# SchematicFinal.net
KiCad netlist of a schematic drawn in EAGLE
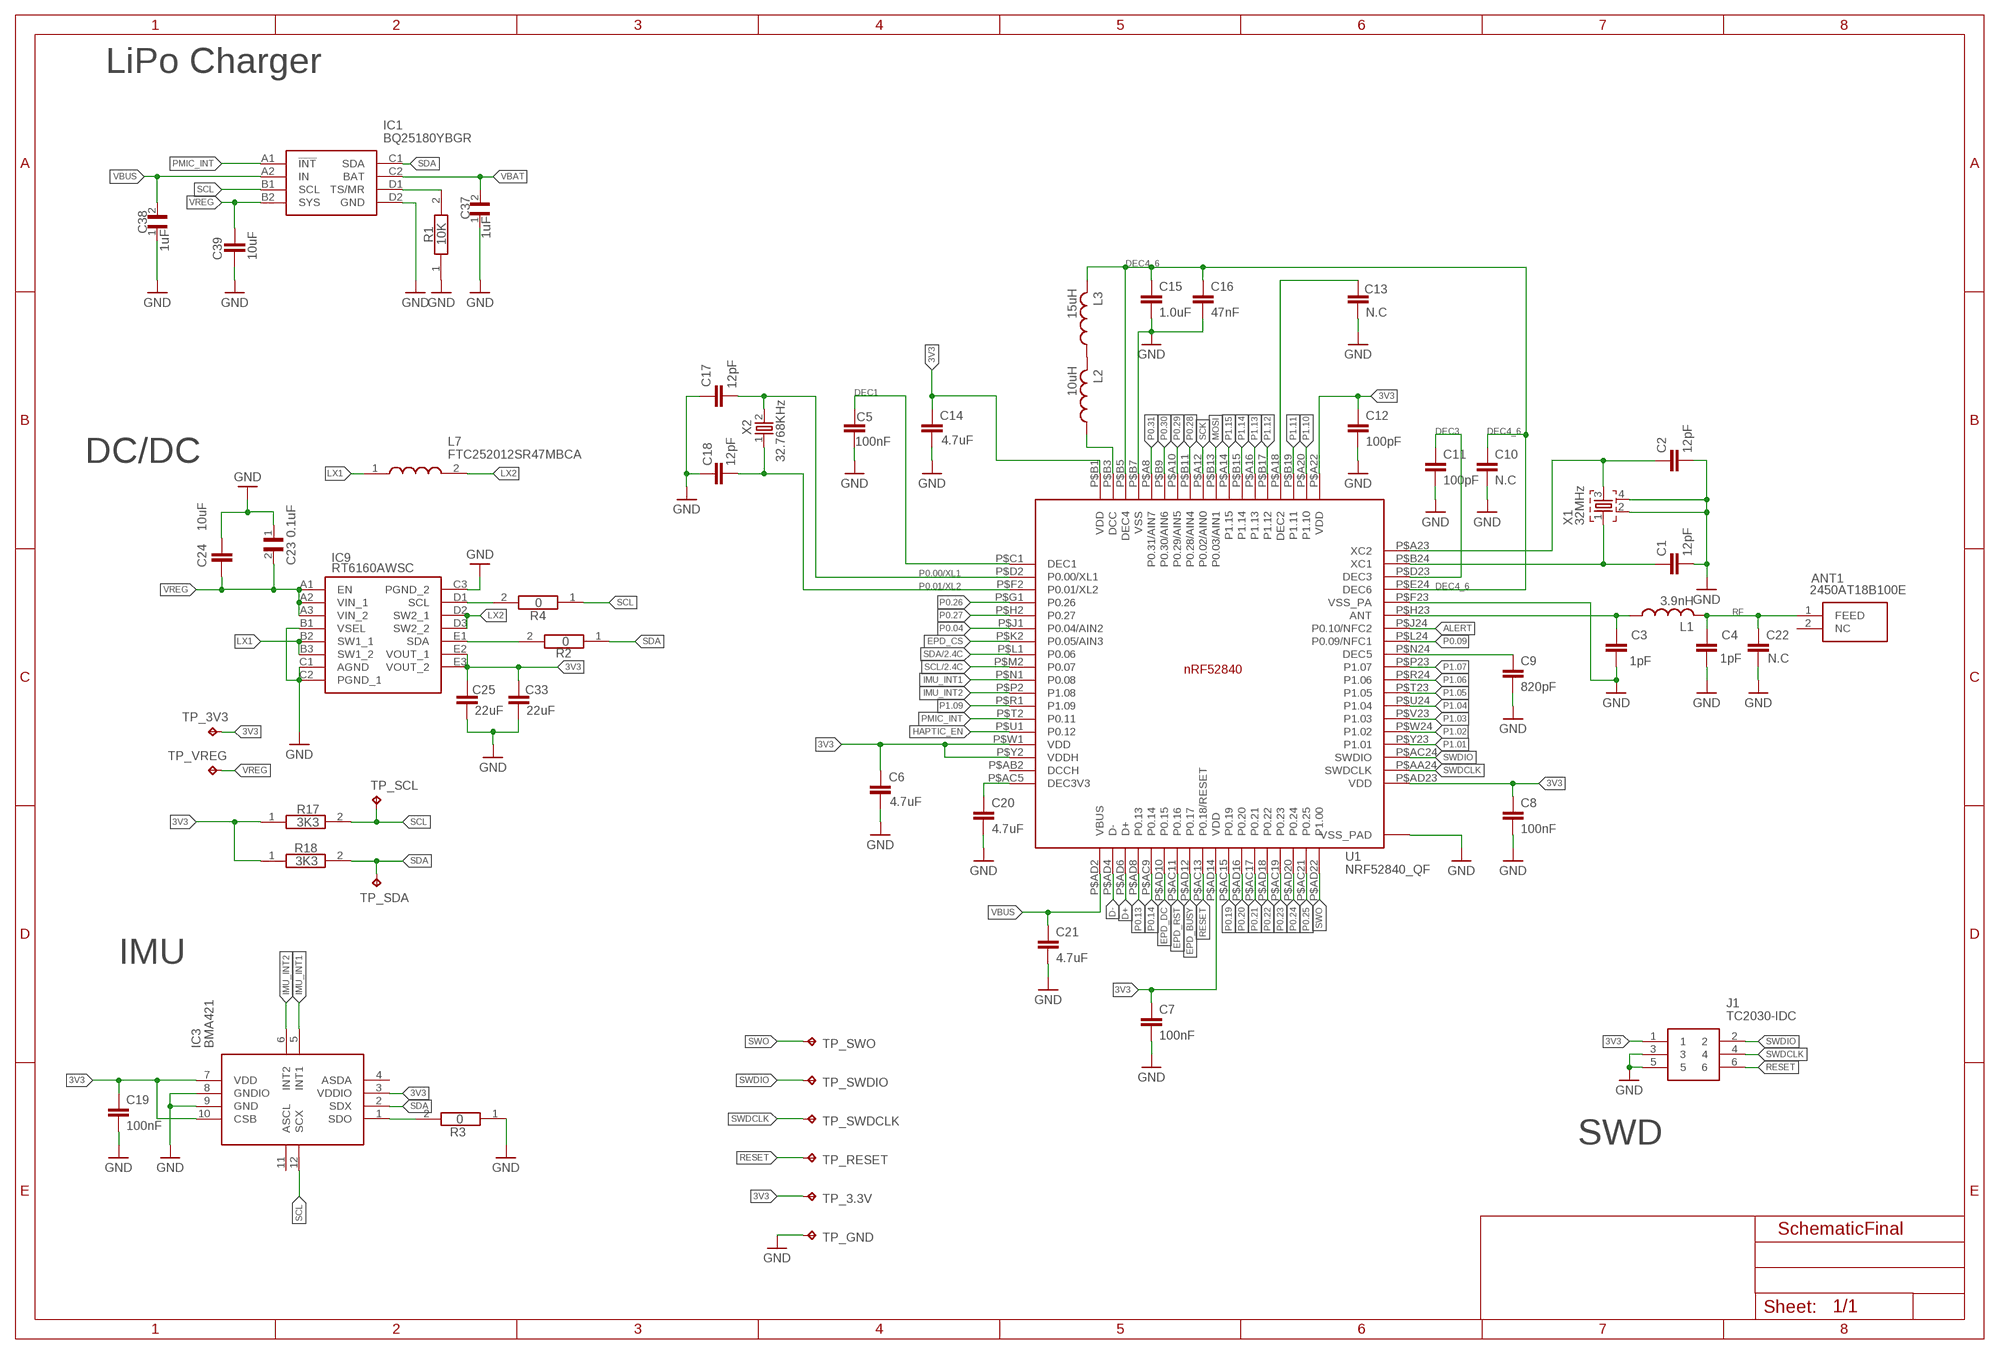
[diagram p0: schematic, sheet 1]

(export (version "E")
  (design (tool "Eeschema 10.0.6"))
  (components
    (comp (ref "ANT1")
      (value "2450AT18B100E")
      (footprint "eagle-import:2450AT18B100E_ANTC3216X140N")
      (fields (field (name "MOUSER_PART_NUMBER") "609-2450AT18B100E"))
      (libsource (lib "eagle-import") (part "2450AT18B100E_2450AT18B100E"))
    )
    (comp (ref "C1")
      (value "12pF")
      (footprint "eagle-import:NORDIC_NRF_3_RESC0402_M")
      (libsource (lib "eagle-import") (part "NORDIC_NRF_3_CAPACITOR_0402_M"))
    )
    (comp (ref "C2")
      (value "12pF")
      (footprint "eagle-import:NORDIC_NRF_3_RESC0402_M")
      (libsource (lib "eagle-import") (part "NORDIC_NRF_3_CAPACITOR_0402_M"))
    )
    (comp (ref "C3")
      (value "1pF")
      (footprint "eagle-import:NORDIC_NRF_3_RESC0402_M")
      (libsource (lib "eagle-import") (part "NORDIC_NRF_3_CAPACITOR_0402_M"))
    )
    (comp (ref "C4")
      (value "1pF")
      (footprint "eagle-import:NORDIC_NRF_3_RESC0402_M")
      (libsource (lib "eagle-import") (part "NORDIC_NRF_3_CAPACITOR_0402_M"))
    )
    (comp (ref "C5")
      (value "100nF")
      (footprint "eagle-import:NORDIC_NRF_3_RESC0402_M")
      (libsource (lib "eagle-import") (part "NORDIC_NRF_3_CAPACITOR_0402_M"))
    )
    (comp (ref "C6")
      (value "4.7uF")
      (footprint "eagle-import:NORDIC_NRF_3_RESC0402_M")
      (libsource (lib "eagle-import") (part "NORDIC_NRF_3_CAPACITOR_0402_M"))
    )
    (comp (ref "C7")
      (value "100nF")
      (footprint "eagle-import:NORDIC_NRF_3_RESC0402_M")
      (libsource (lib "eagle-import") (part "NORDIC_NRF_3_CAPACITOR_0402_M"))
    )
    (comp (ref "C8")
      (value "100nF")
      (footprint "eagle-import:NORDIC_NRF_3_RESC0402_M")
      (libsource (lib "eagle-import") (part "NORDIC_NRF_3_CAPACITOR_0402_M"))
    )
    (comp (ref "C9")
      (value "820pF")
      (footprint "eagle-import:NORDIC_NRF_3_RESC0402_M")
      (libsource (lib "eagle-import") (part "NORDIC_NRF_3_CAPACITOR_0402_M"))
    )
    (comp (ref "C10")
      (value "N.C")
      (footprint "eagle-import:NORDIC_NRF_3_RESC0402_M")
      (libsource (lib "eagle-import") (part "NORDIC_NRF_3_CAPACITOR_0402_M"))
    )
    (comp (ref "C11")
      (value "100pF")
      (footprint "eagle-import:NORDIC_NRF_3_RESC0402_M")
      (libsource (lib "eagle-import") (part "NORDIC_NRF_3_CAPACITOR_0402_M"))
    )
    (comp (ref "C12")
      (value "100pF")
      (footprint "eagle-import:NORDIC_NRF_3_RESC0402_M")
      (libsource (lib "eagle-import") (part "NORDIC_NRF_3_CAPACITOR_0402_M"))
    )
    (comp (ref "C13")
      (value "N.C")
      (footprint "eagle-import:NORDIC_NRF_3_RESC0402_M")
      (libsource (lib "eagle-import") (part "NORDIC_NRF_3_CAPACITOR_0402_M"))
    )
    (comp (ref "C14")
      (value "4.7uF")
      (footprint "eagle-import:NORDIC_NRF_3_RESC0402_M")
      (libsource (lib "eagle-import") (part "NORDIC_NRF_3_CAPACITOR_0402_M"))
    )
    (comp (ref "C15")
      (value "1.0uF")
      (footprint "eagle-import:NORDIC_NRF_3_RESC0402_M")
      (libsource (lib "eagle-import") (part "NORDIC_NRF_3_CAPACITOR_0402_M"))
    )
    (comp (ref "C16")
      (value "47nF")
      (footprint "eagle-import:NORDIC_NRF_3_RESC0402_M")
      (libsource (lib "eagle-import") (part "NORDIC_NRF_3_CAPACITOR_0402_M"))
    )
    (comp (ref "C17")
      (value "12pF")
      (footprint "eagle-import:NORDIC_NRF_3_RESC0402_M")
      (libsource (lib "eagle-import") (part "NORDIC_NRF_3_CAPACITOR_0402_M"))
    )
    (comp (ref "C18")
      (value "12pF")
      (footprint "eagle-import:NORDIC_NRF_3_RESC0402_M")
      (libsource (lib "eagle-import") (part "NORDIC_NRF_3_CAPACITOR_0402_M"))
    )
    (comp (ref "C19")
      (value "100nF")
      (footprint "eagle-import:NORDIC_NRF_3_RESC0402_M")
      (libsource (lib "eagle-import") (part "NORDIC_NRF_3_CAPACITOR_0402_M"))
    )
    (comp (ref "C20")
      (value "4.7uF")
      (footprint "eagle-import:NORDIC_NRF_3_RESC0402_M")
      (libsource (lib "eagle-import") (part "NORDIC_NRF_3_CAPACITOR_0402_M"))
    )
    (comp (ref "C21")
      (value "4.7uF")
      (footprint "eagle-import:NORDIC_NRF_3_RESC0402_M")
      (libsource (lib "eagle-import") (part "NORDIC_NRF_3_CAPACITOR_0402_M"))
    )
    (comp (ref "C22")
      (value "N.C")
      (footprint "eagle-import:NORDIC_NRF_3_RESC0402_M")
      (libsource (lib "eagle-import") (part "NORDIC_NRF_3_CAPACITOR_0402_M"))
    )
    (comp (ref "C23")
      (value "0.1uF")
      (footprint "eagle-import:GRM011R60J152KE01L_2_CAPC0201X13N")
      (fields (field (name "MF") "Murata") (field (name "MP") "GRM011R60J152KE01L"))
      (libsource (lib "eagle-import") (part "GRM011R60J152KE01L_2_GRM011R60J152KE01L"))
    )
    (comp (ref "C24")
      (value "10uF")
      (footprint "eagle-import:NORDIC_NRF_3_RESC0201_M")
      (libsource (lib "eagle-import") (part "InkTime_v5_vf.j4IuITTJRL6_J4EDa8VESQ_NORDIC_NRF_3_CAPACITOR_0201_M"))
    )
    (comp (ref "C25")
      (value "22uF")
      (footprint "eagle-import:NORDIC_NRF_3_RESC0402_M")
      (libsource (lib "eagle-import") (part "NORDIC_NRF_3_CAPACITOR_0402_M"))
    )
    (comp (ref "C33")
      (value "22uF")
      (footprint "eagle-import:NORDIC_NRF_3_RESC0402_M")
      (libsource (lib "eagle-import") (part "NORDIC_NRF_3_CAPACITOR_0402_M"))
    )
    (comp (ref "C37")
      (value "1uF")
      (footprint "eagle-import:GRM011R60J152KE01L_2_CAPC0201X13N")
      (fields (field (name "MF") "Murata") (field (name "MP") "GRM011R60J152KE01L"))
      (libsource (lib "eagle-import") (part "GRM011R60J152KE01L_2_GRM011R60J152KE01L"))
    )
    (comp (ref "C38")
      (value "1uF")
      (footprint "eagle-import:GRM011R60J152KE01L_2_CAPC0201X13N")
      (fields (field (name "MF") "Murata") (field (name "MP") "GRM011R60J152KE01L"))
      (libsource (lib "eagle-import") (part "GRM011R60J152KE01L_2_GRM011R60J152KE01L"))
    )
    (comp (ref "C39")
      (value "10uF")
      (footprint "eagle-import:NORDIC_NRF_3_RESC0402_M")
      (libsource (lib "eagle-import") (part "NORDIC_NRF_3_CAPACITOR_0402_M"))
    )
    (comp (ref "IC1")
      (value "BQ25180YBGR")
      (footprint "eagle-import:BQ25180YBGR_BGA8C40P2X4_100X155X50")
      (fields (field (name "MOUSER_PART_NUMBER") "595-BQ25180YBGR"))
      (libsource (lib "eagle-import") (part "BQ25180YBGR_BQ25180YBGR"))
    )
    (comp (ref "IC3")
      (value "BMA421")
      (footprint "eagle-import:BMA423_BMA423")
      (fields (field (name "ARROW_PART_NUMBER") "BMA423") (field (name "MOUSER_PART_NUMBER") "262-BMA423"))
      (libsource (lib "eagle-import") (part "BMA423_BMA423"))
    )
    (comp (ref "IC9")
      (value "RT6160AWSC")
      (footprint "eagle-import:RT6160AWSC_BGA15C40P3X5_140X230X60")
      (fields (field (name "MOUSER_PART_NUMBER") "835-RT6160AWSC"))
      (libsource (lib "eagle-import") (part "RT6160AWSC_RT6160AWSC"))
    )
    (comp (ref "J1")
      (value "TC2030-IDC")
      (footprint "eagle-import:TC2030-IDC_TC2030IDC")
      (libsource (lib "eagle-import") (part "TC2030-IDC_TC2030-IDC"))
    )
    (comp (ref "L1")
      (value "3.9nH")
      (footprint "eagle-import:NORDIC_NRF_2_RESC0402_M")
      (libsource (lib "eagle-import") (part "NORDIC_NRF_2_INDUCTOR_0402_M"))
    )
    (comp (ref "L2")
      (value "10uH")
      (footprint "eagle-import:NORDIC_NRF_2_RESC0402_M")
      (libsource (lib "eagle-import") (part "NORDIC_NRF_2_INDUCTOR_0402_M"))
    )
    (comp (ref "L3")
      (value "15uH")
      (footprint "eagle-import:NORDIC_NRF_2_RESC0402_M")
      (libsource (lib "eagle-import") (part "NORDIC_NRF_2_INDUCTOR_0402_M"))
    )
    (comp (ref "L7")
      (value "FTC252012SR47MBCA")
      (footprint "eagle-import:MLP2016SR47MT0S1_INDC2016X100N")
      (libsource (lib "eagle-import") (part "MLP2016SR47MT0S1_FTC252012SR47MBCA"))
    )
    (comp (ref "R1")
      (value "10K")
      (footprint "eagle-import:CPF0201D7K68C1_0201")
      (libsource (lib "eagle-import") (part "CPF0201D7K68C1_CPF0201D7K68C1"))
    )
    (comp (ref "R2")
      (value "0")
      (footprint "eagle-import:CPF0201D7K68C1_0201")
      (libsource (lib "eagle-import") (part "CPF0201D7K68C1_CPF0201D7K68C1"))
    )
    (comp (ref "R3")
      (value "0")
      (footprint "eagle-import:CPF0201D7K68C1_0201")
      (libsource (lib "eagle-import") (part "CPF0201D7K68C1_CPF0201D7K68C1"))
    )
    (comp (ref "R4")
      (value "0")
      (footprint "eagle-import:CPF0201D7K68C1_0201")
      (libsource (lib "eagle-import") (part "CPF0201D7K68C1_CPF0201D7K68C1"))
    )
    (comp (ref "R17")
      (value "3K3")
      (footprint "eagle-import:CPF0201D7K68C1_0201")
      (libsource (lib "eagle-import") (part "CPF0201D7K68C1_CPF0201D7K68C1"))
    )
    (comp (ref "R18")
      (value "3K3")
      (footprint "eagle-import:CPF0201D7K68C1_0201")
      (libsource (lib "eagle-import") (part "CPF0201D7K68C1_CPF0201D7K68C1"))
    )
    (comp (ref "TP_3.3V")
      (value "HECTOR_WATCH_1_TPTP20R")
      (footprint "eagle-import:HECTOR_WATCH_1_TP20R")
      (libsource (lib "eagle-import") (part "HECTOR_WATCH_1_TPTP20R"))
    )
    (comp (ref "TP_3V3")
      (value "HECTOR_WATCH_1_TPTP20R")
      (footprint "eagle-import:HECTOR_WATCH_1_TP20R")
      (libsource (lib "eagle-import") (part "HECTOR_WATCH_1_TPTP20R"))
    )
    (comp (ref "TP_GND")
      (value "HECTOR_WATCH_1_TPTP20R")
      (footprint "eagle-import:HECTOR_WATCH_1_TP20R")
      (libsource (lib "eagle-import") (part "HECTOR_WATCH_1_TPTP20R"))
    )
    (comp (ref "TP_RESET")
      (value "HECTOR_WATCH_1_TPTP20R")
      (footprint "eagle-import:HECTOR_WATCH_1_TP20R")
      (libsource (lib "eagle-import") (part "HECTOR_WATCH_1_TPTP20R"))
    )
    (comp (ref "TP_SCL")
      (value "HECTOR_WATCH_1_TPTP20R")
      (footprint "eagle-import:HECTOR_WATCH_1_TP20R")
      (libsource (lib "eagle-import") (part "HECTOR_WATCH_1_TPTP20R"))
    )
    (comp (ref "TP_SDA")
      (value "HECTOR_WATCH_1_TPTP20R")
      (footprint "eagle-import:HECTOR_WATCH_1_TP20R")
      (libsource (lib "eagle-import") (part "HECTOR_WATCH_1_TPTP20R"))
    )
    (comp (ref "TP_SWDCLK")
      (value "HECTOR_WATCH_1_TPTP20R")
      (footprint "eagle-import:HECTOR_WATCH_1_TP20R")
      (libsource (lib "eagle-import") (part "HECTOR_WATCH_1_TPTP20R"))
    )
    (comp (ref "TP_SWDIO")
      (value "HECTOR_WATCH_1_TPTP20R")
      (footprint "eagle-import:HECTOR_WATCH_1_TP20R")
      (libsource (lib "eagle-import") (part "HECTOR_WATCH_1_TPTP20R"))
    )
    (comp (ref "TP_SWO")
      (value "HECTOR_WATCH_1_TPTP20R")
      (footprint "eagle-import:HECTOR_WATCH_1_TP20R")
      (libsource (lib "eagle-import") (part "HECTOR_WATCH_1_TPTP20R"))
    )
    (comp (ref "TP_VREG")
      (value "HECTOR_WATCH_1_TPTP20R")
      (footprint "eagle-import:HECTOR_WATCH_1_TP20R")
      (libsource (lib "eagle-import") (part "HECTOR_WATCH_1_TPTP20R"))
    )
    (comp (ref "U1")
      (value "NRF52840_QF")
      (footprint "eagle-import:NORDIC_NRF_4_AQFN50P700X700X85_HS-74N")
      (libsource (lib "eagle-import") (part "NORDIC_NRF_4_NRF52840_QF"))
    )
    (comp (ref "X1")
      (value "32MHz")
      (footprint "eagle-import:NORDIC_NRF_BT-XTAL_2016_N")
      (libsource (lib "eagle-import") (part "NORDIC_NRF_XTAL_32MHZ"))
    )
    (comp (ref "X2")
      (value "32.768KHz")
      (footprint "eagle-import:NORDIC_NRF_1_XTAL_3215_N")
      (libsource (lib "eagle-import") (part "NORDIC_NRF_1_XTAL_32KHZ"))
    )
  )
  (nets
    (net (code "1") (name "3V3") (class "Default")
      (node (ref "C12") (pin "1") (pinfunction "1_1") (pintype "passive"))
      (node (ref "C14") (pin "2") (pinfunction "2_2") (pintype "passive"))
      (node (ref "C19") (pin "1") (pinfunction "1_1") (pintype "passive"))
      (node (ref "C25") (pin "1") (pinfunction "1_1") (pintype "passive"))
      (node (ref "C33") (pin "1") (pinfunction "1_1") (pintype "passive"))
      (node (ref "C6") (pin "2") (pinfunction "2_2") (pintype "passive"))
      (node (ref "C7") (pin "1") (pinfunction "1_1") (pintype "passive"))
      (node (ref "C8") (pin "1") (pinfunction "1_1") (pintype "passive"))
      (node (ref "IC3") (pin "10") (pinfunction "CSB_10") (pintype "bidirectional"))
      (node (ref "IC3") (pin "3") (pinfunction "VDDIO_3") (pintype "bidirectional"))
      (node (ref "IC3") (pin "7") (pinfunction "VDD_7") (pintype "bidirectional"))
      (node (ref "IC9") (pin "E2") (pinfunction "VOUT_1_E2") (pintype "bidirectional"))
      (node (ref "IC9") (pin "E3") (pinfunction "VOUT_2_E3") (pintype "bidirectional"))
      (node (ref "J1") (pin "1") (pinfunction "1_1") (pintype "bidirectional"))
      (node (ref "R17") (pin "1") (pinfunction "1_1") (pintype "bidirectional"))
      (node (ref "R18") (pin "1") (pinfunction "1_1") (pintype "bidirectional"))
      (node (ref "TP_3.3V") (pin "TP") (pinfunction "TP_TP") (pintype "input"))
      (node (ref "TP_3V3") (pin "TP") (pinfunction "TP_TP") (pintype "input"))
      (node (ref "U1") (pin "P$A22") (pinfunction "VDD_P$A22") (pintype "power_in"))
      (node (ref "U1") (pin "P$AD14") (pinfunction "VDD_P$AD14") (pintype "power_in"))
      (node (ref "U1") (pin "P$AD23") (pinfunction "VDD_P$AD23") (pintype "power_in"))
      (node (ref "U1") (pin "P$B1") (pinfunction "VDD_P$B1") (pintype "power_in"))
      (node (ref "U1") (pin "P$W1") (pinfunction "VDD_P$W1") (pintype "power_in"))
      (node (ref "U1") (pin "P$Y2") (pinfunction "VDDH_P$Y2") (pintype "power_in"))
    )
    (net (code "2") (name "ALERT") (class "Default")
      (node (ref "U1") (pin "P$J24") (pinfunction "P0.10/NFC2_P$J24") (pintype "bidirectional"))
    )
    (net (code "3") (name "D+") (class "Default")
      (node (ref "U1") (pin "P$AD6") (pinfunction "D+_P$AD6") (pintype "bidirectional"))
    )
    (net (code "4") (name "D-") (class "Default")
      (node (ref "U1") (pin "P$AD4") (pinfunction "D-_P$AD4") (pintype "bidirectional"))
    )
    (net (code "5") (name "EPD_BUSY") (class "Default")
      (node (ref "U1") (pin "P$AD12") (pinfunction "P0.17_P$AD12") (pintype "bidirectional"))
    )
    (net (code "6") (name "EPD_CS") (class "Default")
      (node (ref "U1") (pin "P$K2") (pinfunction "P0.05/AIN3_P$K2") (pintype "bidirectional"))
    )
    (net (code "7") (name "EPD_DC") (class "Default")
      (node (ref "U1") (pin "P$AD10") (pinfunction "P0.15_P$AD10") (pintype "bidirectional"))
    )
    (net (code "8") (name "EPD_RST") (class "Default")
      (node (ref "U1") (pin "P$AC11") (pinfunction "P0.16_P$AC11") (pintype "bidirectional"))
    )
    (net (code "9") (name "GND") (class "Default")
      (node (ref "C1") (pin "2") (pinfunction "2_2") (pintype "passive"))
      (node (ref "C10") (pin "2") (pinfunction "2_2") (pintype "passive"))
      (node (ref "C11") (pin "2") (pinfunction "2_2") (pintype "passive"))
      (node (ref "C12") (pin "2") (pinfunction "2_2") (pintype "passive"))
      (node (ref "C13") (pin "2") (pinfunction "2_2") (pintype "passive"))
      (node (ref "C14") (pin "1") (pinfunction "1_1") (pintype "passive"))
      (node (ref "C15") (pin "2") (pinfunction "2_2") (pintype "passive"))
      (node (ref "C16") (pin "2") (pinfunction "2_2") (pintype "passive"))
      (node (ref "C17") (pin "2") (pinfunction "2_2") (pintype "passive"))
      (node (ref "C18") (pin "2") (pinfunction "2_2") (pintype "passive"))
      (node (ref "C19") (pin "2") (pinfunction "2_2") (pintype "passive"))
      (node (ref "C2") (pin "2") (pinfunction "2_2") (pintype "passive"))
      (node (ref "C20") (pin "1") (pinfunction "1_1") (pintype "passive"))
      (node (ref "C21") (pin "2") (pinfunction "2_2") (pintype "passive"))
      (node (ref "C22") (pin "1") (pinfunction "1_1") (pintype "passive"))
      (node (ref "C23") (pin "1") (pinfunction "1_1") (pintype "passive"))
      (node (ref "C24") (pin "1") (pinfunction "1_1") (pintype "passive"))
      (node (ref "C25") (pin "2") (pinfunction "2_2") (pintype "passive"))
      (node (ref "C3") (pin "1") (pinfunction "1_1") (pintype "passive"))
      (node (ref "C33") (pin "2") (pinfunction "2_2") (pintype "passive"))
      (node (ref "C37") (pin "1") (pinfunction "1_1") (pintype "passive"))
      (node (ref "C38") (pin "1") (pinfunction "1_1") (pintype "passive"))
      (node (ref "C39") (pin "2") (pinfunction "2_2") (pintype "passive"))
      (node (ref "C4") (pin "1") (pinfunction "1_1") (pintype "passive"))
      (node (ref "C5") (pin "1") (pinfunction "1_1") (pintype "passive"))
      (node (ref "C6") (pin "1") (pinfunction "1_1") (pintype "passive"))
      (node (ref "C7") (pin "2") (pinfunction "2_2") (pintype "passive"))
      (node (ref "C8") (pin "2") (pinfunction "2_2") (pintype "passive"))
      (node (ref "C9") (pin "2") (pinfunction "2_2") (pintype "passive"))
      (node (ref "IC1") (pin "D2") (pinfunction "GND_D2") (pintype "bidirectional"))
      (node (ref "IC3") (pin "8") (pinfunction "GNDIO_8") (pintype "bidirectional"))
      (node (ref "IC3") (pin "9") (pinfunction "GND_9") (pintype "bidirectional"))
      (node (ref "IC9") (pin "B1") (pinfunction "VSEL_B1") (pintype "bidirectional"))
      (node (ref "IC9") (pin "C1") (pinfunction "AGND_C1") (pintype "bidirectional"))
      (node (ref "IC9") (pin "C2") (pinfunction "PGND_1_C2") (pintype "bidirectional"))
      (node (ref "IC9") (pin "C3") (pinfunction "PGND_2_C3") (pintype "bidirectional"))
      (node (ref "J1") (pin "3") (pinfunction "3_3") (pintype "bidirectional"))
      (node (ref "J1") (pin "5") (pinfunction "5_5") (pintype "bidirectional"))
      (node (ref "R1") (pin "1") (pinfunction "1_1") (pintype "bidirectional"))
      (node (ref "R3") (pin "1") (pinfunction "1_1") (pintype "bidirectional"))
      (node (ref "TP_GND") (pin "TP") (pinfunction "TP_TP") (pintype "input"))
      (node (ref "U1") (pin "P$74") (pinfunction "VSS_PAD_P$74") (pintype "bidirectional"))
      (node (ref "U1") (pin "P$75") (pinfunction "VSS_PAD_P$75") (pintype "bidirectional"))
      (node (ref "U1") (pin "P$76") (pinfunction "VSS_PAD_P$76") (pintype "bidirectional"))
      (node (ref "U1") (pin "P$77") (pinfunction "VSS_PAD_P$77") (pintype "bidirectional"))
      (node (ref "U1") (pin "P$78") (pinfunction "VSS_PAD_P$78") (pintype "bidirectional"))
      (node (ref "U1") (pin "P$79") (pinfunction "VSS_PAD_P$79") (pintype "bidirectional"))
      (node (ref "U1") (pin "P$80") (pinfunction "VSS_PAD_P$80") (pintype "bidirectional"))
      (node (ref "U1") (pin "P$81") (pinfunction "VSS_PAD_P$81") (pintype "bidirectional"))
      (node (ref "U1") (pin "P$82") (pinfunction "VSS_PAD_P$82") (pintype "bidirectional"))
      (node (ref "U1") (pin "P$83") (pinfunction "VSS_PAD_P$83") (pintype "bidirectional"))
      (node (ref "U1") (pin "P$84") (pinfunction "VSS_PAD_P$84") (pintype "bidirectional"))
      (node (ref "U1") (pin "P$85") (pinfunction "VSS_PAD_P$85") (pintype "bidirectional"))
      (node (ref "U1") (pin "P$86") (pinfunction "VSS_PAD_P$86") (pintype "bidirectional"))
      (node (ref "U1") (pin "P$87") (pinfunction "VSS_PAD_P$87") (pintype "bidirectional"))
      (node (ref "U1") (pin "P$88") (pinfunction "VSS_PAD_P$88") (pintype "bidirectional"))
      (node (ref "U1") (pin "P$89") (pinfunction "VSS_PAD_P$89") (pintype "bidirectional"))
      (node (ref "U1") (pin "P$90") (pinfunction "VSS_PAD_P$90") (pintype "bidirectional"))
      (node (ref "U1") (pin "P$B7") (pinfunction "VSS_P$B7") (pintype "power_in"))
      (node (ref "U1") (pin "P$F23") (pinfunction "VSS_PA_P$F23") (pintype "bidirectional"))
      (node (ref "X1") (pin "2") (pinfunction "2_2") (pintype "passive"))
      (node (ref "X1") (pin "4") (pinfunction "4_4") (pintype "passive"))
    )
    (net (code "10") (name "HAPTIC_EN") (class "Default")
      (node (ref "U1") (pin "P$U1") (pinfunction "P0.12_P$U1") (pintype "bidirectional"))
    )
    (net (code "11") (name "IMU_INT1") (class "Default")
      (node (ref "IC3") (pin "5") (pinfunction "INT1_5") (pintype "bidirectional"))
      (node (ref "U1") (pin "P$N1") (pinfunction "P0.08_P$N1") (pintype "bidirectional"))
    )
    (net (code "12") (name "IMU_INT2") (class "Default")
      (node (ref "IC3") (pin "6") (pinfunction "INT2_6") (pintype "bidirectional"))
      (node (ref "U1") (pin "P$P2") (pinfunction "P1.08_P$P2") (pintype "bidirectional"))
    )
    (net (code "13") (name "LX1") (class "Default")
      (node (ref "IC9") (pin "B2") (pinfunction "SW1_1_B2") (pintype "bidirectional"))
      (node (ref "IC9") (pin "B3") (pinfunction "SW1_2_B3") (pintype "bidirectional"))
      (node (ref "L7") (pin "1") (pinfunction "1_1") (pintype "bidirectional"))
    )
    (net (code "14") (name "LX2") (class "Default")
      (node (ref "IC9") (pin "D2") (pinfunction "SW2_1_D2") (pintype "bidirectional"))
      (node (ref "IC9") (pin "D3") (pinfunction "SW2_2_D3") (pintype "bidirectional"))
      (node (ref "L7") (pin "2") (pinfunction "2_2") (pintype "bidirectional"))
    )
    (net (code "15") (name "MOSI") (class "Default")
      (node (ref "U1") (pin "P$B13") (pinfunction "P0.03/AIN1_P$B13") (pintype "bidirectional"))
    )
    (net (code "16") (name "Net-(ANT1-FEED)") (class "Default")
      (node (ref "ANT1") (pin "1") (pinfunction "FEED_1") (pintype "input"))
      (node (ref "C22") (pin "2") (pinfunction "2_2") (pintype "passive"))
      (node (ref "C4") (pin "2") (pinfunction "2_2") (pintype "passive"))
      (node (ref "L1") (pin "2") (pinfunction "2_2") (pintype "passive"))
    )
    (net (code "17") (name "Net-(IC1-TS{slash}MR)") (class "Default")
      (node (ref "IC1") (pin "D1") (pinfunction "TS/MR_D1") (pintype "bidirectional"))
      (node (ref "R1") (pin "2") (pinfunction "2_2") (pintype "bidirectional"))
    )
    (net (code "18") (name "Net-(IC3-SDO)") (class "Default")
      (node (ref "IC3") (pin "1") (pinfunction "SDO_1") (pintype "bidirectional"))
      (node (ref "R3") (pin "2") (pinfunction "2_2") (pintype "bidirectional"))
    )
    (net (code "19") (name "Net-(IC9-SCL)") (class "Default")
      (node (ref "IC9") (pin "D1") (pinfunction "SCL_D1") (pintype "bidirectional"))
      (node (ref "R4") (pin "2") (pinfunction "2_2") (pintype "bidirectional"))
    )
    (net (code "20") (name "Net-(IC9-SDA)") (class "Default")
      (node (ref "IC9") (pin "E1") (pinfunction "SDA_E1") (pintype "bidirectional"))
      (node (ref "R2") (pin "2") (pinfunction "2_2") (pintype "bidirectional"))
    )
    (net (code "21") (name "Net-(L2-Pad1)") (class "Default")
      (node (ref "L2") (pin "1") (pinfunction "1_1") (pintype "passive"))
      (node (ref "L3") (pin "2") (pinfunction "2_2") (pintype "passive"))
    )
    (net (code "22") (name "Net-(U1-ANT)") (class "Default")
      (node (ref "C3") (pin "2") (pinfunction "2_2") (pintype "passive"))
      (node (ref "L1") (pin "1") (pinfunction "1_1") (pintype "passive"))
      (node (ref "U1") (pin "P$H23") (pinfunction "ANT_P$H23") (pintype "bidirectional"))
    )
    (net (code "23") (name "Net-(U1-DCC)") (class "Default")
      (node (ref "L2") (pin "2") (pinfunction "2_2") (pintype "passive"))
      (node (ref "U1") (pin "P$B3") (pinfunction "DCC_P$B3") (pintype "output"))
    )
    (net (code "24") (name "Net-(U1-DEC1)") (class "Default")
      (node (ref "C5") (pin "2") (pinfunction "2_2") (pintype "passive"))
      (node (ref "U1") (pin "P$C1") (pinfunction "DEC1_P$C1") (pintype "power_in"))
    )
    (net (code "25") (name "Net-(U1-DEC2)") (class "Default")
      (node (ref "C13") (pin "1") (pinfunction "1_1") (pintype "passive"))
      (node (ref "U1") (pin "P$A18") (pinfunction "DEC2_P$A18") (pintype "bidirectional"))
    )
    (net (code "26") (name "Net-(U1-DEC3)") (class "Default")
      (node (ref "C11") (pin "1") (pinfunction "1_1") (pintype "passive"))
      (node (ref "U1") (pin "P$D23") (pinfunction "DEC3_P$D23") (pintype "bidirectional"))
    )
    (net (code "27") (name "Net-(U1-DEC3V3)") (class "Default")
      (node (ref "C20") (pin "2") (pinfunction "2_2") (pintype "passive"))
      (node (ref "U1") (pin "P$AC5") (pinfunction "DEC3V3_P$AC5") (pintype "bidirectional"))
    )
    (net (code "28") (name "Net-(U1-DEC4)") (class "Default")
      (node (ref "C10") (pin "1") (pinfunction "1_1") (pintype "passive"))
      (node (ref "C15") (pin "1") (pinfunction "1_1") (pintype "passive"))
      (node (ref "C16") (pin "1") (pinfunction "1_1") (pintype "passive"))
      (node (ref "L3") (pin "1") (pinfunction "1_1") (pintype "passive"))
      (node (ref "U1") (pin "P$B5") (pinfunction "DEC4_P$B5") (pintype "power_in"))
      (node (ref "U1") (pin "P$E24") (pinfunction "DEC6_P$E24") (pintype "bidirectional"))
    )
    (net (code "29") (name "Net-(U1-DEC5)") (class "Default")
      (node (ref "C9") (pin "1") (pinfunction "1_1") (pintype "passive"))
      (node (ref "U1") (pin "P$N24") (pinfunction "DEC5_P$N24") (pintype "bidirectional"))
    )
    (net (code "30") (name "Net-(U1-P0.00{slash}XL1)") (class "Default")
      (node (ref "C17") (pin "1") (pinfunction "1_1") (pintype "passive"))
      (node (ref "U1") (pin "P$D2") (pinfunction "P0.00/XL1_P$D2") (pintype "bidirectional"))
      (node (ref "X2") (pin "2") (pinfunction "2_2") (pintype "passive"))
    )
    (net (code "31") (name "Net-(U1-P0.01{slash}XL2)") (class "Default")
      (node (ref "C18") (pin "1") (pinfunction "1_1") (pintype "passive"))
      (node (ref "U1") (pin "P$F2") (pinfunction "P0.01/XL2_P$F2") (pintype "bidirectional"))
      (node (ref "X2") (pin "1") (pinfunction "1_1") (pintype "passive"))
    )
    (net (code "32") (name "Net-(U1-XC1)") (class "Default")
      (node (ref "C1") (pin "1") (pinfunction "1_1") (pintype "passive"))
      (node (ref "U1") (pin "P$B24") (pinfunction "XC1_P$B24") (pintype "input"))
      (node (ref "X1") (pin "1") (pinfunction "1_1") (pintype "passive"))
    )
    (net (code "33") (name "Net-(U1-XC2)") (class "Default")
      (node (ref "C2") (pin "1") (pinfunction "1_1") (pintype "passive"))
      (node (ref "U1") (pin "P$A23") (pinfunction "XC2_P$A23") (pintype "output"))
      (node (ref "X1") (pin "3") (pinfunction "3_3") (pintype "passive"))
    )
    (net (code "34") (name "P0.04") (class "Default")
      (node (ref "U1") (pin "P$J1") (pinfunction "P0.04/AIN2_P$J1") (pintype "bidirectional"))
    )
    (net (code "35") (name "P0.09") (class "Default")
      (node (ref "U1") (pin "P$L24") (pinfunction "P0.09/NFC1_P$L24") (pintype "bidirectional"))
    )
    (net (code "36") (name "P0.13") (class "Default")
      (node (ref "U1") (pin "P$AD8") (pinfunction "P0.13_P$AD8") (pintype "bidirectional"))
    )
    (net (code "37") (name "P0.14") (class "Default")
      (node (ref "U1") (pin "P$AC9") (pinfunction "P0.14_P$AC9") (pintype "bidirectional"))
    )
    (net (code "38") (name "P0.19") (class "Default")
      (node (ref "U1") (pin "P$AC15") (pinfunction "P0.19_P$AC15") (pintype "bidirectional"))
    )
    (net (code "39") (name "P0.20") (class "Default")
      (node (ref "U1") (pin "P$AD16") (pinfunction "P0.20_P$AD16") (pintype "bidirectional"))
    )
    (net (code "40") (name "P0.21") (class "Default")
      (node (ref "U1") (pin "P$AC17") (pinfunction "P0.21_P$AC17") (pintype "bidirectional"))
    )
    (net (code "41") (name "P0.22") (class "Default")
      (node (ref "U1") (pin "P$AD18") (pinfunction "P0.22_P$AD18") (pintype "bidirectional"))
    )
    (net (code "42") (name "P0.23") (class "Default")
      (node (ref "U1") (pin "P$AC19") (pinfunction "P0.23_P$AC19") (pintype "bidirectional"))
    )
    (net (code "43") (name "P0.24") (class "Default")
      (node (ref "U1") (pin "P$AD20") (pinfunction "P0.24_P$AD20") (pintype "bidirectional"))
    )
    (net (code "44") (name "P0.25") (class "Default")
      (node (ref "U1") (pin "P$AC21") (pinfunction "P0.25_P$AC21") (pintype "bidirectional"))
    )
    (net (code "45") (name "P0.26") (class "Default")
      (node (ref "U1") (pin "P$G1") (pinfunction "P0.26_P$G1") (pintype "bidirectional"))
    )
    (net (code "46") (name "P0.27") (class "Default")
      (node (ref "U1") (pin "P$H2") (pinfunction "P0.27_P$H2") (pintype "bidirectional"))
    )
    (net (code "47") (name "P0.28") (class "Default")
      (node (ref "U1") (pin "P$B11") (pinfunction "P0.28/AIN4_P$B11") (pintype "bidirectional"))
    )
    (net (code "48") (name "P0.29") (class "Default")
      (node (ref "U1") (pin "P$A10") (pinfunction "P0.29/AIN5_P$A10") (pintype "bidirectional"))
    )
    (net (code "49") (name "P0.30") (class "Default")
      (node (ref "U1") (pin "P$B9") (pinfunction "P0.30/AIN6_P$B9") (pintype "bidirectional"))
    )
    (net (code "50") (name "P0.31") (class "Default")
      (node (ref "U1") (pin "P$A8") (pinfunction "P0.31/AIN7_P$A8") (pintype "bidirectional"))
    )
    (net (code "51") (name "P1.01") (class "Default")
      (node (ref "U1") (pin "P$Y23") (pinfunction "P1.01_P$Y23") (pintype "bidirectional"))
    )
    (net (code "52") (name "P1.02") (class "Default")
      (node (ref "U1") (pin "P$W24") (pinfunction "P1.02_P$W24") (pintype "bidirectional"))
    )
    (net (code "53") (name "P1.03") (class "Default")
      (node (ref "U1") (pin "P$V23") (pinfunction "P1.03_P$V23") (pintype "bidirectional"))
    )
    (net (code "54") (name "P1.04") (class "Default")
      (node (ref "U1") (pin "P$U24") (pinfunction "P1.04_P$U24") (pintype "bidirectional"))
    )
    (net (code "55") (name "P1.05") (class "Default")
      (node (ref "U1") (pin "P$T23") (pinfunction "P1.05_P$T23") (pintype "bidirectional"))
    )
    (net (code "56") (name "P1.06") (class "Default")
      (node (ref "U1") (pin "P$R24") (pinfunction "P1.06_P$R24") (pintype "bidirectional"))
    )
    (net (code "57") (name "P1.07") (class "Default")
      (node (ref "U1") (pin "P$P23") (pinfunction "P1.07_P$P23") (pintype "bidirectional"))
    )
    (net (code "58") (name "P1.09") (class "Default")
      (node (ref "U1") (pin "P$R1") (pinfunction "P1.09_P$R1") (pintype "bidirectional"))
    )
    (net (code "59") (name "P1.10") (class "Default")
      (node (ref "U1") (pin "P$A20") (pinfunction "P1.10_P$A20") (pintype "bidirectional"))
    )
    (net (code "60") (name "P1.11") (class "Default")
      (node (ref "U1") (pin "P$B19") (pinfunction "P1.11_P$B19") (pintype "bidirectional"))
    )
    (net (code "61") (name "P1.12") (class "Default")
      (node (ref "U1") (pin "P$B17") (pinfunction "P1.12_P$B17") (pintype "bidirectional"))
    )
    (net (code "62") (name "P1.13") (class "Default")
      (node (ref "U1") (pin "P$A16") (pinfunction "P1.13_P$A16") (pintype "bidirectional"))
    )
    (net (code "63") (name "P1.14") (class "Default")
      (node (ref "U1") (pin "P$B15") (pinfunction "P1.14_P$B15") (pintype "bidirectional"))
    )
    (net (code "64") (name "P1.15") (class "Default")
      (node (ref "U1") (pin "P$A14") (pinfunction "P1.15_P$A14") (pintype "bidirectional"))
    )
    (net (code "65") (name "PMIC_INT") (class "Default")
      (node (ref "IC1") (pin "A1") (pinfunction "~{INT}_A1") (pintype "bidirectional"))
      (node (ref "U1") (pin "P$T2") (pinfunction "P0.11_P$T2") (pintype "bidirectional"))
    )
    (net (code "66") (name "RESET") (class "Default")
      (node (ref "J1") (pin "6") (pinfunction "6_6") (pintype "bidirectional"))
      (node (ref "TP_RESET") (pin "TP") (pinfunction "TP_TP") (pintype "input"))
      (node (ref "U1") (pin "P$AC13") (pinfunction "P0.18/RESET_P$AC13") (pintype "bidirectional"))
    )
    (net (code "67") (name "SCK") (class "Default")
      (node (ref "U1") (pin "P$A12") (pinfunction "P0.02/AIN0_P$A12") (pintype "bidirectional"))
    )
    (net (code "68") (name "SCL") (class "Default")
      (node (ref "IC1") (pin "B1") (pinfunction "SCL_B1") (pintype "bidirectional"))
      (node (ref "IC3") (pin "12") (pinfunction "SCX_12") (pintype "bidirectional"))
      (node (ref "R17") (pin "2") (pinfunction "2_2") (pintype "bidirectional"))
      (node (ref "R4") (pin "1") (pinfunction "1_1") (pintype "bidirectional"))
      (node (ref "TP_SCL") (pin "TP") (pinfunction "TP_TP") (pintype "input"))
    )
    (net (code "69") (name "SCL{slash}2.4C") (class "Default")
      (node (ref "U1") (pin "P$M2") (pinfunction "P0.07_P$M2") (pintype "bidirectional"))
    )
    (net (code "70") (name "SDA") (class "Default")
      (node (ref "IC1") (pin "C1") (pinfunction "SDA_C1") (pintype "bidirectional"))
      (node (ref "IC3") (pin "2") (pinfunction "SDX_2") (pintype "bidirectional"))
      (node (ref "R18") (pin "2") (pinfunction "2_2") (pintype "bidirectional"))
      (node (ref "R2") (pin "1") (pinfunction "1_1") (pintype "bidirectional"))
      (node (ref "TP_SDA") (pin "TP") (pinfunction "TP_TP") (pintype "input"))
    )
    (net (code "71") (name "SDA{slash}2.4C") (class "Default")
      (node (ref "U1") (pin "P$L1") (pinfunction "P0.06_P$L1") (pintype "bidirectional"))
    )
    (net (code "72") (name "SWDCLK") (class "Default")
      (node (ref "J1") (pin "4") (pinfunction "4_4") (pintype "bidirectional"))
      (node (ref "TP_SWDCLK") (pin "TP") (pinfunction "TP_TP") (pintype "input"))
      (node (ref "U1") (pin "P$AA24") (pinfunction "SWDCLK_P$AA24") (pintype "input"))
    )
    (net (code "73") (name "SWDIO") (class "Default")
      (node (ref "J1") (pin "2") (pinfunction "2_2") (pintype "bidirectional"))
      (node (ref "TP_SWDIO") (pin "TP") (pinfunction "TP_TP") (pintype "input"))
      (node (ref "U1") (pin "P$AC24") (pinfunction "SWDIO_P$AC24") (pintype "bidirectional"))
    )
    (net (code "74") (name "SWO") (class "Default")
      (node (ref "TP_SWO") (pin "TP") (pinfunction "TP_TP") (pintype "input"))
      (node (ref "U1") (pin "P$AD22") (pinfunction "P1.00_P$AD22") (pintype "bidirectional"))
    )
    (net (code "75") (name "VBAT") (class "Default")
      (node (ref "C37") (pin "2") (pinfunction "2_2") (pintype "passive"))
      (node (ref "IC1") (pin "C2") (pinfunction "BAT_C2") (pintype "bidirectional"))
    )
    (net (code "76") (name "VBUS") (class "Default")
      (node (ref "C21") (pin "1") (pinfunction "1_1") (pintype "passive"))
      (node (ref "C38") (pin "2") (pinfunction "2_2") (pintype "passive"))
      (node (ref "IC1") (pin "A2") (pinfunction "IN_A2") (pintype "bidirectional"))
      (node (ref "U1") (pin "P$AD2") (pinfunction "VBUS_P$AD2") (pintype "power_in"))
    )
    (net (code "77") (name "VREG") (class "Default")
      (node (ref "C23") (pin "2") (pinfunction "2_2") (pintype "passive"))
      (node (ref "C24") (pin "2") (pinfunction "2_2") (pintype "passive"))
      (node (ref "C39") (pin "1") (pinfunction "1_1") (pintype "passive"))
      (node (ref "IC1") (pin "B2") (pinfunction "SYS_B2") (pintype "bidirectional"))
      (node (ref "IC9") (pin "A1") (pinfunction "EN_A1") (pintype "bidirectional"))
      (node (ref "IC9") (pin "A2") (pinfunction "VIN_1_A2") (pintype "bidirectional"))
      (node (ref "IC9") (pin "A3") (pinfunction "VIN_2_A3") (pintype "bidirectional"))
      (node (ref "TP_VREG") (pin "TP") (pinfunction "TP_TP") (pintype "input"))
    )
    (net (code "78") (name "unconnected-(ANT1-NC-Pad2)") (class "Default")
      (node (ref "ANT1") (pin "2") (pinfunction "NC_2") (pintype "no_connect"))
    )
    (net (code "79") (name "unconnected-(IC3-ASCL-Pad11)") (class "Default")
      (node (ref "IC3") (pin "11") (pinfunction "ASCL_11") (pintype "bidirectional"))
    )
    (net (code "80") (name "unconnected-(IC3-ASDA-Pad4)") (class "Default")
      (node (ref "IC3") (pin "4") (pinfunction "ASDA_4") (pintype "bidirectional"))
    )
    (net (code "81") (name "unconnected-(U1-DCCH-PadP$AB2)") (class "Default")
      (node (ref "U1") (pin "P$AB2") (pinfunction "DCCH_P$AB2") (pintype "bidirectional"))
    )
  )
)
